# PCB-ETHMG-BOS.net
KiCad netlist of a schematic drawn in EAGLE
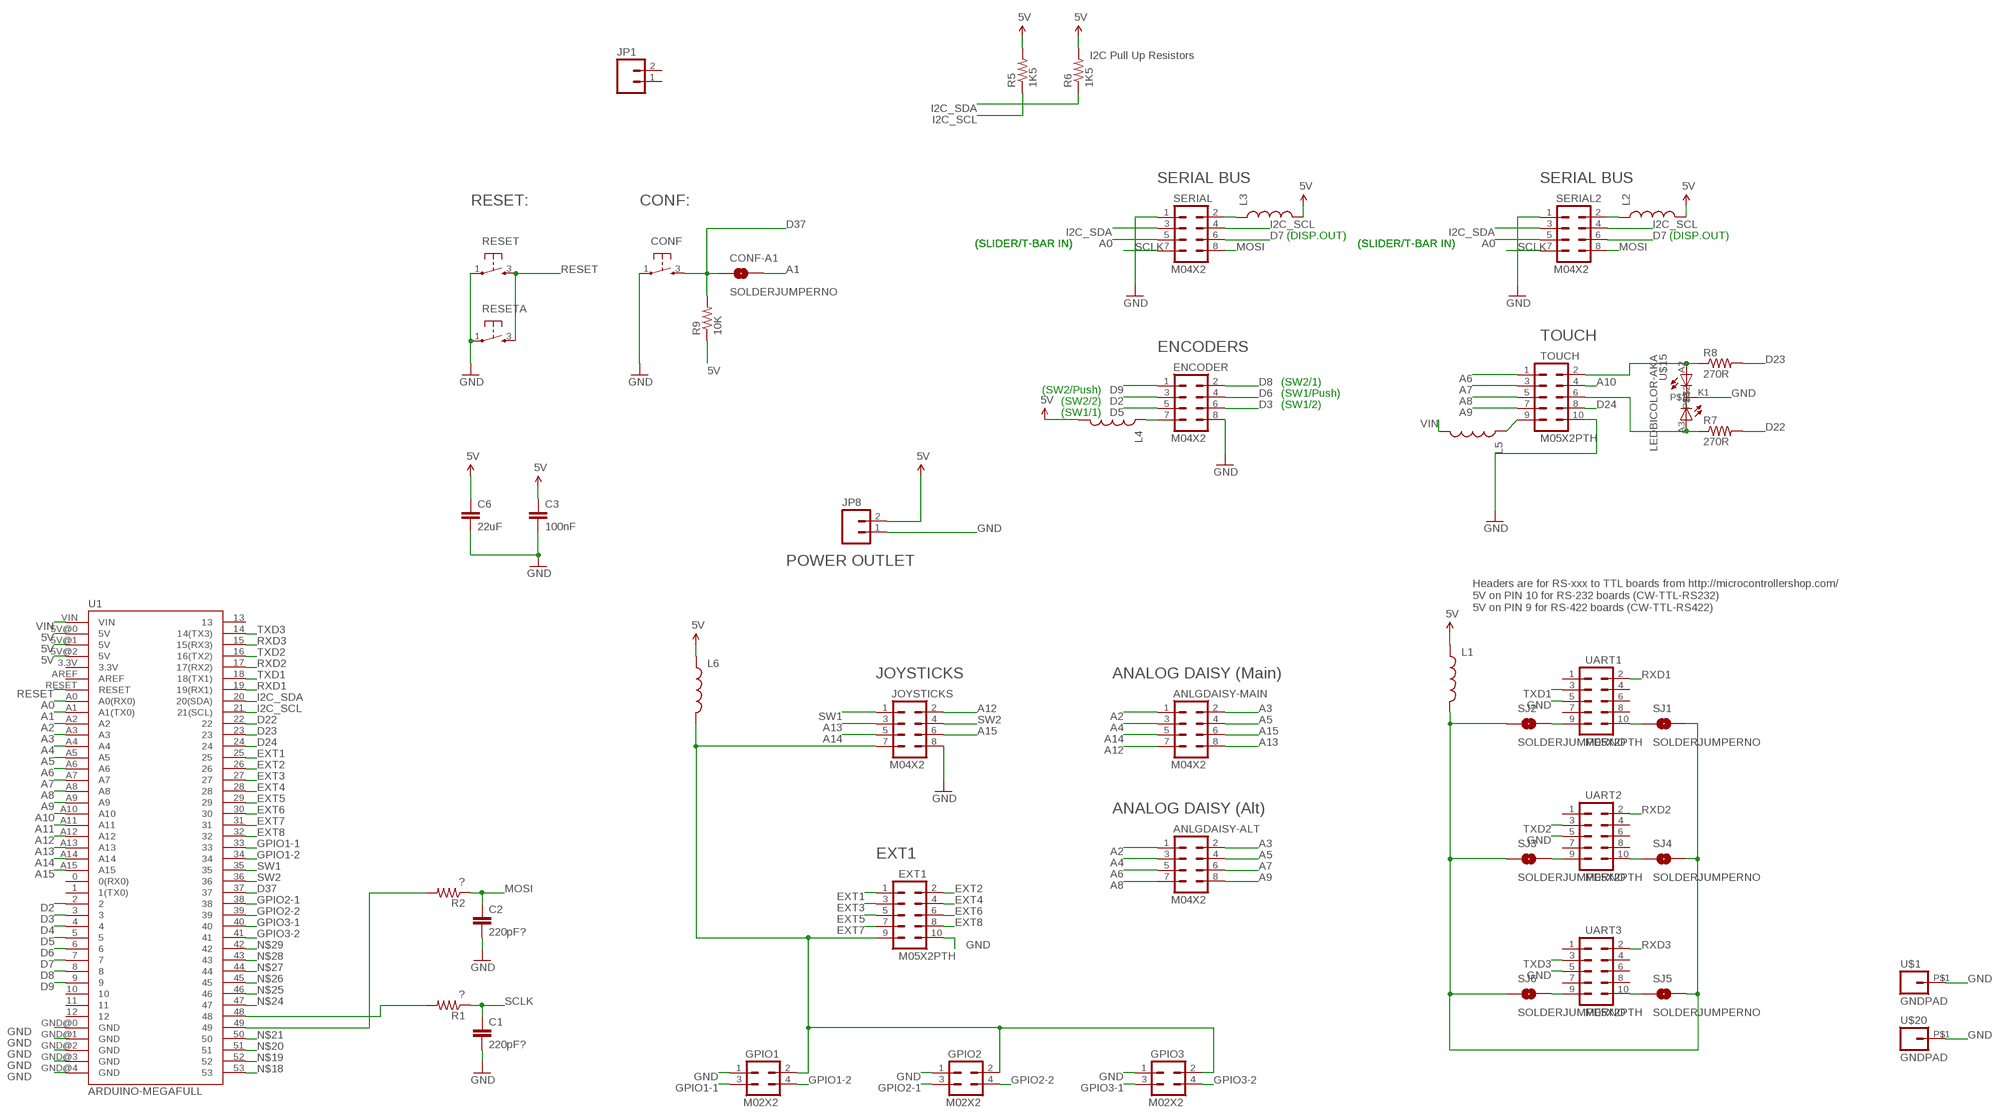
[diagram p0: schematic, sheet 1]

(export (version "E")
  (design (tool "Eeschema 10.0.6"))
  (components
    (comp (ref "ANLGDAISY-ALT")
      (value "M04X2")
      (footprint "eagle-import:2X4")
      (libsource (lib "eagle-import") (part "M04X2"))
    )
    (comp (ref "ANLGDAISY-MAIN")
      (value "M04X2")
      (footprint "eagle-import:2X4")
      (libsource (lib "eagle-import") (part "M04X2"))
    )
    (comp (ref "C1")
      (value "220pF?")
      (footprint "eagle-import:0603-CAP")
      (libsource (lib "eagle-import") (part "CAP0603-CAP"))
    )
    (comp (ref "C2")
      (value "220pF?")
      (footprint "eagle-import:0603-CAP")
      (libsource (lib "eagle-import") (part "CAP0603-CAP"))
    )
    (comp (ref "C3")
      (value "100nF")
      (footprint "eagle-import:0603-CAP")
      (libsource (lib "eagle-import") (part "CAP0603-CAP"))
    )
    (comp (ref "C6")
      (value "22uF")
      (footprint "eagle-import:0805")
      (libsource (lib "eagle-import") (part "CAP0805"))
    )
    (comp (ref "CONF")
      (value "TAC_SWITCH")
      (footprint "eagle-import:PUSHBUTTON")
      (libsource (lib "eagle-import") (part "TAC_SWITCH"))
    )
    (comp (ref "CONF-A1")
      (value "SOLDERJUMPERNO")
      (footprint "eagle-import:SJ_2S-NO")
      (libsource (lib "eagle-import") (part "SOLDERJUMPERNO"))
    )
    (comp (ref "ENCODER")
      (value "M04X2")
      (footprint "eagle-import:2X4")
      (libsource (lib "eagle-import") (part "M04X2"))
    )
    (comp (ref "EXT1")
      (value "M05X2PTH")
      (footprint "eagle-import:AVR_ICSP")
      (libsource (lib "eagle-import") (part "M05X2PTH"))
    )
    (comp (ref "GPIO1")
      (value "M02X2")
      (footprint "eagle-import:2X2")
      (libsource (lib "eagle-import") (part "M02X2"))
    )
    (comp (ref "GPIO2")
      (value "M02X2")
      (footprint "eagle-import:2X2")
      (libsource (lib "eagle-import") (part "M02X2"))
    )
    (comp (ref "GPIO3")
      (value "M02X2")
      (footprint "eagle-import:2X2")
      (libsource (lib "eagle-import") (part "M02X2"))
    )
    (comp (ref "JOYSTICKS")
      (value "M04X2")
      (footprint "eagle-import:2X4")
      (libsource (lib "eagle-import") (part "M04X2"))
    )
    (comp (ref "JP1")
      (value "M02PTH")
      (footprint "eagle-import:1X02")
      (libsource (lib "eagle-import") (part "M02PTH"))
    )
    (comp (ref "JP8")
      (value "M02PTH4")
      (footprint "eagle-import:1X02_XTRA_BIG")
      (libsource (lib "eagle-import") (part "M02PTH4"))
    )
    (comp (ref "L1")
      (value "INDUCTOR0805")
      (footprint "eagle-import:0805")
      (libsource (lib "eagle-import") (part "INDUCTOR0805"))
    )
    (comp (ref "L2")
      (value "INDUCTOR0805")
      (footprint "eagle-import:0805")
      (libsource (lib "eagle-import") (part "INDUCTOR0805"))
    )
    (comp (ref "L3")
      (value "INDUCTOR0805")
      (footprint "eagle-import:0805")
      (libsource (lib "eagle-import") (part "INDUCTOR0805"))
    )
    (comp (ref "L4")
      (value "INDUCTOR0805")
      (footprint "eagle-import:0805")
      (libsource (lib "eagle-import") (part "INDUCTOR0805"))
    )
    (comp (ref "L5")
      (value "INDUCTOR0805")
      (footprint "eagle-import:0805")
      (libsource (lib "eagle-import") (part "INDUCTOR0805"))
    )
    (comp (ref "L6")
      (value "INDUCTOR0805")
      (footprint "eagle-import:0805")
      (libsource (lib "eagle-import") (part "INDUCTOR0805"))
    )
    (comp (ref "R1")
      (value "?")
      (footprint "eagle-import:0603-RES")
      (libsource (lib "eagle-import") (part "RESISTOR0603-RES"))
    )
    (comp (ref "R2")
      (value "?")
      (footprint "eagle-import:0603-RES")
      (libsource (lib "eagle-import") (part "RESISTOR0603-RES"))
    )
    (comp (ref "R5")
      (value "1K5")
      (footprint "eagle-import:0603-RES")
      (libsource (lib "eagle-import") (part "RESISTOR0603-RES"))
    )
    (comp (ref "R6")
      (value "1K5")
      (footprint "eagle-import:0603-RES")
      (libsource (lib "eagle-import") (part "RESISTOR0603-RES"))
    )
    (comp (ref "R7")
      (value "270R")
      (footprint "eagle-import:0603-RES")
      (libsource (lib "eagle-import") (part "RESISTOR0603-RES"))
    )
    (comp (ref "R8")
      (value "270R")
      (footprint "eagle-import:0603-RES")
      (libsource (lib "eagle-import") (part "RESISTOR0603-RES"))
    )
    (comp (ref "R9")
      (value "10K")
      (footprint "eagle-import:0603-RES")
      (libsource (lib "eagle-import") (part "RESISTOR0603-RES"))
    )
    (comp (ref "RESET")
      (value "TAC_SWITCH")
      (footprint "eagle-import:PUSHBUTTON")
      (libsource (lib "eagle-import") (part "TAC_SWITCH"))
    )
    (comp (ref "RESETA")
      (value "TAC_SWITCH")
      (footprint "eagle-import:PUSHBUTTON")
      (libsource (lib "eagle-import") (part "TAC_SWITCH"))
    )
    (comp (ref "SERIAL")
      (value "M04X2")
      (footprint "eagle-import:2X4")
      (libsource (lib "eagle-import") (part "M04X2"))
    )
    (comp (ref "SERIAL2")
      (value "M04X2")
      (footprint "eagle-import:2X4")
      (libsource (lib "eagle-import") (part "M04X2"))
    )
    (comp (ref "SJ1")
      (value "SOLDERJUMPERNO")
      (footprint "eagle-import:SJ_2S-NO")
      (libsource (lib "eagle-import") (part "SOLDERJUMPERNO"))
    )
    (comp (ref "SJ2")
      (value "SOLDERJUMPERNO")
      (footprint "eagle-import:SJ_2S-NO")
      (libsource (lib "eagle-import") (part "SOLDERJUMPERNO"))
    )
    (comp (ref "SJ3")
      (value "SOLDERJUMPERNO")
      (footprint "eagle-import:SJ_2S-NO")
      (libsource (lib "eagle-import") (part "SOLDERJUMPERNO"))
    )
    (comp (ref "SJ4")
      (value "SOLDERJUMPERNO")
      (footprint "eagle-import:SJ_2S-NO")
      (libsource (lib "eagle-import") (part "SOLDERJUMPERNO"))
    )
    (comp (ref "SJ5")
      (value "SOLDERJUMPERNO")
      (footprint "eagle-import:SJ_2S-NO")
      (libsource (lib "eagle-import") (part "SOLDERJUMPERNO"))
    )
    (comp (ref "SJ6")
      (value "SOLDERJUMPERNO")
      (footprint "eagle-import:SJ_2S-NO")
      (libsource (lib "eagle-import") (part "SOLDERJUMPERNO"))
    )
    (comp (ref "TOUCH")
      (value "M05X2PTH")
      (footprint "eagle-import:AVR_ICSP")
      (libsource (lib "eagle-import") (part "M05X2PTH"))
    )
    (comp (ref "U$1")
      (value "GNDPAD")
      (footprint "eagle-import:3.2MMPAD")
      (libsource (lib "eagle-import") (part "GNDPAD"))
    )
    (comp (ref "U$15")
      (value "LEDBICOLOR-AKA")
      (footprint "eagle-import:LED5MM-BICOLOR")
      (libsource (lib "eagle-import") (part "LEDBICOLOR-AKA"))
    )
    (comp (ref "U$20")
      (value "GNDPAD")
      (footprint "eagle-import:3.2MMPAD")
      (libsource (lib "eagle-import") (part "GNDPAD"))
    )
    (comp (ref "U1")
      (value "ARDUINO-MEGAFULL")
      (footprint "eagle-import:ARDUINO_MEGA")
      (libsource (lib "eagle-import") (part "ARDUINO-MEGAFULL"))
    )
    (comp (ref "UART1")
      (value "M05X2PTH")
      (footprint "eagle-import:AVR_ICSP")
      (libsource (lib "eagle-import") (part "M05X2PTH"))
    )
    (comp (ref "UART2")
      (value "M05X2PTH")
      (footprint "eagle-import:AVR_ICSP")
      (libsource (lib "eagle-import") (part "M05X2PTH"))
    )
    (comp (ref "UART3")
      (value "M05X2PTH")
      (footprint "eagle-import:AVR_ICSP")
      (libsource (lib "eagle-import") (part "M05X2PTH"))
    )
  )
  (nets
    (net (code "1") (name "/A0") (class "Default")
      (node (ref "SERIAL") (pin "5") (pinfunction "5_5") (pintype "passive"))
      (node (ref "SERIAL2") (pin "5") (pinfunction "5_5") (pintype "passive"))
      (node (ref "U1") (pin "A0") (pinfunction "A0(RX0)_A0") (pintype "bidirectional"))
    )
    (net (code "2") (name "/A1") (class "Default")
      (node (ref "CONF-A1") (pin "2") (pinfunction "2_2") (pintype "passive"))
      (node (ref "U1") (pin "A1") (pinfunction "A1(TX0)_A1") (pintype "bidirectional"))
    )
    (net (code "3") (name "/A2") (class "Default")
      (node (ref "ANLGDAISY-ALT") (pin "1") (pinfunction "1_1") (pintype "passive"))
      (node (ref "ANLGDAISY-MAIN") (pin "1") (pinfunction "1_1") (pintype "passive"))
      (node (ref "U1") (pin "A2") (pinfunction "A2_A2") (pintype "bidirectional"))
    )
    (net (code "4") (name "/A3") (class "Default")
      (node (ref "ANLGDAISY-ALT") (pin "2") (pinfunction "2_2") (pintype "passive"))
      (node (ref "ANLGDAISY-MAIN") (pin "2") (pinfunction "2_2") (pintype "passive"))
      (node (ref "U1") (pin "A3") (pinfunction "A3_A3") (pintype "bidirectional"))
    )
    (net (code "5") (name "/A4") (class "Default")
      (node (ref "ANLGDAISY-ALT") (pin "3") (pinfunction "3_3") (pintype "passive"))
      (node (ref "ANLGDAISY-MAIN") (pin "3") (pinfunction "3_3") (pintype "passive"))
      (node (ref "U1") (pin "A4") (pinfunction "A4_A4") (pintype "bidirectional"))
    )
    (net (code "6") (name "/A5") (class "Default")
      (node (ref "ANLGDAISY-ALT") (pin "4") (pinfunction "4_4") (pintype "passive"))
      (node (ref "ANLGDAISY-MAIN") (pin "4") (pinfunction "4_4") (pintype "passive"))
      (node (ref "U1") (pin "A5") (pinfunction "A5_A5") (pintype "bidirectional"))
    )
    (net (code "7") (name "/A6") (class "Default")
      (node (ref "ANLGDAISY-ALT") (pin "5") (pinfunction "5_5") (pintype "passive"))
      (node (ref "TOUCH") (pin "1") (pinfunction "1_1") (pintype "passive"))
      (node (ref "U1") (pin "A6") (pinfunction "A6_A6") (pintype "bidirectional"))
    )
    (net (code "8") (name "/A7") (class "Default")
      (node (ref "ANLGDAISY-ALT") (pin "6") (pinfunction "6_6") (pintype "passive"))
      (node (ref "TOUCH") (pin "3") (pinfunction "3_3") (pintype "passive"))
      (node (ref "U1") (pin "A7") (pinfunction "A7_A7") (pintype "bidirectional"))
    )
    (net (code "9") (name "/A8") (class "Default")
      (node (ref "ANLGDAISY-ALT") (pin "7") (pinfunction "7_7") (pintype "passive"))
      (node (ref "TOUCH") (pin "5") (pinfunction "5_5") (pintype "passive"))
      (node (ref "U1") (pin "A8") (pinfunction "A8_A8") (pintype "bidirectional"))
    )
    (net (code "10") (name "/A9") (class "Default")
      (node (ref "ANLGDAISY-ALT") (pin "8") (pinfunction "8_8") (pintype "passive"))
      (node (ref "TOUCH") (pin "7") (pinfunction "7_7") (pintype "passive"))
      (node (ref "U1") (pin "A9") (pinfunction "A9_A9") (pintype "bidirectional"))
    )
    (net (code "11") (name "/A10") (class "Default")
      (node (ref "TOUCH") (pin "4") (pinfunction "4_4") (pintype "passive"))
      (node (ref "U1") (pin "A10") (pinfunction "A10_A10") (pintype "bidirectional"))
    )
    (net (code "12") (name "/A11") (class "Default")
      (node (ref "U1") (pin "A11") (pinfunction "A11_A11") (pintype "bidirectional"))
    )
    (net (code "13") (name "/A12") (class "Default")
      (node (ref "ANLGDAISY-MAIN") (pin "7") (pinfunction "7_7") (pintype "passive"))
      (node (ref "JOYSTICKS") (pin "2") (pinfunction "2_2") (pintype "passive"))
      (node (ref "U1") (pin "A12") (pinfunction "A12_A12") (pintype "bidirectional"))
    )
    (net (code "14") (name "/A13") (class "Default")
      (node (ref "ANLGDAISY-MAIN") (pin "8") (pinfunction "8_8") (pintype "passive"))
      (node (ref "JOYSTICKS") (pin "3") (pinfunction "3_3") (pintype "passive"))
      (node (ref "U1") (pin "A13") (pinfunction "A13_A13") (pintype "bidirectional"))
    )
    (net (code "15") (name "/A14") (class "Default")
      (node (ref "ANLGDAISY-MAIN") (pin "5") (pinfunction "5_5") (pintype "passive"))
      (node (ref "JOYSTICKS") (pin "5") (pinfunction "5_5") (pintype "passive"))
      (node (ref "U1") (pin "A14") (pinfunction "A14_A14") (pintype "bidirectional"))
    )
    (net (code "16") (name "/A15") (class "Default")
      (node (ref "ANLGDAISY-MAIN") (pin "6") (pinfunction "6_6") (pintype "passive"))
      (node (ref "JOYSTICKS") (pin "6") (pinfunction "6_6") (pintype "passive"))
      (node (ref "U1") (pin "A15") (pinfunction "A15_A15") (pintype "bidirectional"))
    )
    (net (code "17") (name "/D2") (class "Default")
      (node (ref "ENCODER") (pin "3") (pinfunction "3_3") (pintype "passive"))
      (node (ref "U1") (pin "2") (pinfunction "2_2") (pintype "bidirectional"))
    )
    (net (code "18") (name "/D3") (class "Default")
      (node (ref "ENCODER") (pin "6") (pinfunction "6_6") (pintype "passive"))
      (node (ref "U1") (pin "3") (pinfunction "3_3") (pintype "bidirectional"))
    )
    (net (code "19") (name "/D4") (class "Default")
      (node (ref "U1") (pin "4") (pinfunction "4_4") (pintype "bidirectional"))
    )
    (net (code "20") (name "/D5") (class "Default")
      (node (ref "ENCODER") (pin "5") (pinfunction "5_5") (pintype "passive"))
      (node (ref "U1") (pin "5") (pinfunction "5_5") (pintype "bidirectional"))
    )
    (net (code "21") (name "/D6") (class "Default")
      (node (ref "ENCODER") (pin "4") (pinfunction "4_4") (pintype "passive"))
      (node (ref "U1") (pin "6") (pinfunction "6_6") (pintype "bidirectional"))
    )
    (net (code "22") (name "/D7") (class "Default")
      (node (ref "SERIAL") (pin "6") (pinfunction "6_6") (pintype "passive"))
      (node (ref "SERIAL2") (pin "6") (pinfunction "6_6") (pintype "passive"))
      (node (ref "U1") (pin "7") (pinfunction "7_7") (pintype "bidirectional"))
    )
    (net (code "23") (name "/D8") (class "Default")
      (node (ref "ENCODER") (pin "2") (pinfunction "2_2") (pintype "passive"))
      (node (ref "U1") (pin "8") (pinfunction "8_8") (pintype "bidirectional"))
    )
    (net (code "24") (name "/D9") (class "Default")
      (node (ref "ENCODER") (pin "1") (pinfunction "1_1") (pintype "passive"))
      (node (ref "U1") (pin "9") (pinfunction "9_9") (pintype "bidirectional"))
    )
    (net (code "25") (name "/D22") (class "Default")
      (node (ref "R7") (pin "2") (pinfunction "2_2") (pintype "passive"))
      (node (ref "U1") (pin "22") (pinfunction "22_22") (pintype "bidirectional"))
    )
    (net (code "26") (name "/D23") (class "Default")
      (node (ref "R8") (pin "2") (pinfunction "2_2") (pintype "passive"))
      (node (ref "U1") (pin "23") (pinfunction "23_23") (pintype "bidirectional"))
    )
    (net (code "27") (name "/D24") (class "Default")
      (node (ref "TOUCH") (pin "8") (pinfunction "8_8") (pintype "passive"))
      (node (ref "U1") (pin "24") (pinfunction "24_24") (pintype "bidirectional"))
    )
    (net (code "28") (name "/D37") (class "Default")
      (node (ref "CONF") (pin "3") (pinfunction "3_3") (pintype "passive"))
      (node (ref "CONF-A1") (pin "1") (pinfunction "1_1") (pintype "passive"))
      (node (ref "R9") (pin "2") (pinfunction "2_2") (pintype "passive"))
      (node (ref "U1") (pin "37") (pinfunction "37_37") (pintype "bidirectional"))
    )
    (net (code "29") (name "/EXT1") (class "Default")
      (node (ref "EXT1") (pin "1") (pinfunction "1_1") (pintype "passive"))
      (node (ref "U1") (pin "25") (pinfunction "25_25") (pintype "bidirectional"))
    )
    (net (code "30") (name "/EXT2") (class "Default")
      (node (ref "EXT1") (pin "2") (pinfunction "2_2") (pintype "passive"))
      (node (ref "U1") (pin "26") (pinfunction "26_26") (pintype "bidirectional"))
    )
    (net (code "31") (name "/EXT3") (class "Default")
      (node (ref "EXT1") (pin "3") (pinfunction "3_3") (pintype "passive"))
      (node (ref "U1") (pin "27") (pinfunction "27_27") (pintype "bidirectional"))
    )
    (net (code "32") (name "/EXT4") (class "Default")
      (node (ref "EXT1") (pin "4") (pinfunction "4_4") (pintype "passive"))
      (node (ref "U1") (pin "28") (pinfunction "28_28") (pintype "bidirectional"))
    )
    (net (code "33") (name "/EXT5") (class "Default")
      (node (ref "EXT1") (pin "5") (pinfunction "5_5") (pintype "passive"))
      (node (ref "U1") (pin "29") (pinfunction "29_29") (pintype "bidirectional"))
    )
    (net (code "34") (name "/EXT6") (class "Default")
      (node (ref "EXT1") (pin "6") (pinfunction "6_6") (pintype "passive"))
      (node (ref "U1") (pin "30") (pinfunction "30_30") (pintype "bidirectional"))
    )
    (net (code "35") (name "/EXT7") (class "Default")
      (node (ref "EXT1") (pin "7") (pinfunction "7_7") (pintype "passive"))
      (node (ref "U1") (pin "31") (pinfunction "31_31") (pintype "bidirectional"))
    )
    (net (code "36") (name "/EXT8") (class "Default")
      (node (ref "EXT1") (pin "8") (pinfunction "8_8") (pintype "passive"))
      (node (ref "U1") (pin "32") (pinfunction "32_32") (pintype "bidirectional"))
    )
    (net (code "37") (name "/GPIO1-1") (class "Default")
      (node (ref "GPIO1") (pin "3") (pinfunction "3_3") (pintype "passive"))
      (node (ref "U1") (pin "33") (pinfunction "33_33") (pintype "bidirectional"))
    )
    (net (code "38") (name "/GPIO1-2") (class "Default")
      (node (ref "GPIO1") (pin "4") (pinfunction "4_4") (pintype "passive"))
      (node (ref "U1") (pin "34") (pinfunction "34_34") (pintype "bidirectional"))
    )
    (net (code "39") (name "/GPIO2-1") (class "Default")
      (node (ref "GPIO2") (pin "3") (pinfunction "3_3") (pintype "passive"))
      (node (ref "U1") (pin "38") (pinfunction "38_38") (pintype "bidirectional"))
    )
    (net (code "40") (name "/GPIO2-2") (class "Default")
      (node (ref "GPIO2") (pin "4") (pinfunction "4_4") (pintype "passive"))
      (node (ref "U1") (pin "39") (pinfunction "39_39") (pintype "bidirectional"))
    )
    (net (code "41") (name "/GPIO3-1") (class "Default")
      (node (ref "GPIO3") (pin "3") (pinfunction "3_3") (pintype "passive"))
      (node (ref "U1") (pin "40") (pinfunction "40_40") (pintype "bidirectional"))
    )
    (net (code "42") (name "/GPIO3-2") (class "Default")
      (node (ref "GPIO3") (pin "4") (pinfunction "4_4") (pintype "passive"))
      (node (ref "U1") (pin "41") (pinfunction "41_41") (pintype "bidirectional"))
    )
    (net (code "43") (name "/I2C_SCL") (class "Default")
      (node (ref "R5") (pin "1") (pinfunction "1_1") (pintype "passive"))
      (node (ref "SERIAL") (pin "4") (pinfunction "4_4") (pintype "passive"))
      (node (ref "SERIAL2") (pin "4") (pinfunction "4_4") (pintype "passive"))
      (node (ref "U1") (pin "21") (pinfunction "21(SCL)_21") (pintype "bidirectional"))
    )
    (net (code "44") (name "/I2C_SDA") (class "Default")
      (node (ref "R6") (pin "1") (pinfunction "1_1") (pintype "passive"))
      (node (ref "SERIAL") (pin "3") (pinfunction "3_3") (pintype "passive"))
      (node (ref "SERIAL2") (pin "3") (pinfunction "3_3") (pintype "passive"))
      (node (ref "U1") (pin "20") (pinfunction "20(SDA)_20") (pintype "bidirectional"))
    )
    (net (code "45") (name "/MOSI") (class "Default")
      (node (ref "C2") (pin "1") (pinfunction "1_1") (pintype "passive"))
      (node (ref "R2") (pin "1") (pinfunction "1_1") (pintype "passive"))
      (node (ref "SERIAL") (pin "8") (pinfunction "8_8") (pintype "passive"))
      (node (ref "SERIAL2") (pin "8") (pinfunction "8_8") (pintype "passive"))
    )
    (net (code "46") (name "/N$18") (class "Default")
      (node (ref "U1") (pin "53") (pinfunction "53_53") (pintype "bidirectional"))
    )
    (net (code "47") (name "/N$19") (class "Default")
      (node (ref "U1") (pin "52") (pinfunction "52_52") (pintype "bidirectional"))
    )
    (net (code "48") (name "/N$20") (class "Default")
      (node (ref "U1") (pin "51") (pinfunction "51_51") (pintype "bidirectional"))
    )
    (net (code "49") (name "/N$21") (class "Default")
      (node (ref "U1") (pin "50") (pinfunction "50_50") (pintype "bidirectional"))
    )
    (net (code "50") (name "/N$24") (class "Default")
      (node (ref "U1") (pin "47") (pinfunction "47_47") (pintype "bidirectional"))
    )
    (net (code "51") (name "/N$25") (class "Default")
      (node (ref "U1") (pin "46") (pinfunction "46_46") (pintype "bidirectional"))
    )
    (net (code "52") (name "/N$26") (class "Default")
      (node (ref "U1") (pin "45") (pinfunction "45_45") (pintype "bidirectional"))
    )
    (net (code "53") (name "/N$27") (class "Default")
      (node (ref "U1") (pin "44") (pinfunction "44_44") (pintype "bidirectional"))
    )
    (net (code "54") (name "/N$28") (class "Default")
      (node (ref "U1") (pin "43") (pinfunction "43_43") (pintype "bidirectional"))
    )
    (net (code "55") (name "/N$29") (class "Default")
      (node (ref "U1") (pin "42") (pinfunction "42_42") (pintype "bidirectional"))
    )
    (net (code "56") (name "/RESET") (class "Default")
      (node (ref "RESET") (pin "3") (pinfunction "3_3") (pintype "passive"))
      (node (ref "RESETA") (pin "3") (pinfunction "3_3") (pintype "passive"))
      (node (ref "U1") (pin "RESET") (pinfunction "RESET_RESET") (pintype "bidirectional"))
    )
    (net (code "57") (name "/RXD1") (class "Default")
      (node (ref "U1") (pin "19") (pinfunction "19(RX1)_19") (pintype "bidirectional"))
      (node (ref "UART1") (pin "2") (pinfunction "2_2") (pintype "passive"))
    )
    (net (code "58") (name "/RXD2") (class "Default")
      (node (ref "U1") (pin "17") (pinfunction "17(RX2)_17") (pintype "bidirectional"))
      (node (ref "UART2") (pin "2") (pinfunction "2_2") (pintype "passive"))
    )
    (net (code "59") (name "/RXD3") (class "Default")
      (node (ref "U1") (pin "15") (pinfunction "15(RX3)_15") (pintype "bidirectional"))
      (node (ref "UART3") (pin "2") (pinfunction "2_2") (pintype "passive"))
    )
    (net (code "60") (name "/SCLK") (class "Default")
      (node (ref "C1") (pin "1") (pinfunction "1_1") (pintype "passive"))
      (node (ref "R1") (pin "1") (pinfunction "1_1") (pintype "passive"))
      (node (ref "SERIAL") (pin "7") (pinfunction "7_7") (pintype "passive"))
      (node (ref "SERIAL2") (pin "7") (pinfunction "7_7") (pintype "passive"))
    )
    (net (code "61") (name "/SW1") (class "Default")
      (node (ref "JOYSTICKS") (pin "1") (pinfunction "1_1") (pintype "passive"))
      (node (ref "U1") (pin "35") (pinfunction "35_35") (pintype "bidirectional"))
    )
    (net (code "62") (name "/SW2") (class "Default")
      (node (ref "JOYSTICKS") (pin "4") (pinfunction "4_4") (pintype "passive"))
      (node (ref "U1") (pin "36") (pinfunction "36_36") (pintype "bidirectional"))
    )
    (net (code "63") (name "/TXD1") (class "Default")
      (node (ref "U1") (pin "18") (pinfunction "18(TX1)_18") (pintype "bidirectional"))
      (node (ref "UART1") (pin "3") (pinfunction "3_3") (pintype "passive"))
    )
    (net (code "64") (name "/TXD2") (class "Default")
      (node (ref "U1") (pin "16") (pinfunction "16(TX2)_16") (pintype "bidirectional"))
      (node (ref "UART2") (pin "3") (pinfunction "3_3") (pintype "passive"))
    )
    (net (code "65") (name "/TXD3") (class "Default")
      (node (ref "U1") (pin "14") (pinfunction "14(TX3)_14") (pintype "bidirectional"))
      (node (ref "UART3") (pin "3") (pinfunction "3_3") (pintype "passive"))
    )
    (net (code "66") (name "/VIN") (class "Default")
      (node (ref "L5") (pin "2") (pinfunction "2_2") (pintype "passive"))
      (node (ref "U1") (pin "VIN") (pinfunction "VIN_VIN") (pintype "bidirectional"))
    )
    (net (code "67") (name "5V") (class "Default")
      (node (ref "C3") (pin "1") (pinfunction "1_1") (pintype "passive"))
      (node (ref "C6") (pin "1") (pinfunction "1_1") (pintype "passive"))
      (node (ref "JP8") (pin "2") (pinfunction "2_2") (pintype "passive"))
      (node (ref "L1") (pin "1") (pinfunction "1_1") (pintype "passive"))
      (node (ref "L2") (pin "2") (pinfunction "2_2") (pintype "passive"))
      (node (ref "L3") (pin "2") (pinfunction "2_2") (pintype "passive"))
      (node (ref "L4") (pin "2") (pinfunction "2_2") (pintype "passive"))
      (node (ref "L6") (pin "1") (pinfunction "1_1") (pintype "passive"))
      (node (ref "R5") (pin "2") (pinfunction "2_2") (pintype "passive"))
      (node (ref "R6") (pin "2") (pinfunction "2_2") (pintype "passive"))
      (node (ref "R9") (pin "1") (pinfunction "1_1") (pintype "passive"))
      (node (ref "U1") (pin "5V@0") (pinfunction "5V_5V@0") (pintype "bidirectional"))
      (node (ref "U1") (pin "5V@1") (pinfunction "5V_5V@1") (pintype "bidirectional"))
      (node (ref "U1") (pin "5V@2") (pinfunction "5V_5V@2") (pintype "bidirectional"))
    )
    (net (code "68") (name "GND") (class "Default")
      (node (ref "C1") (pin "2") (pinfunction "2_2") (pintype "passive"))
      (node (ref "C2") (pin "2") (pinfunction "2_2") (pintype "passive"))
      (node (ref "C3") (pin "2") (pinfunction "2_2") (pintype "passive"))
      (node (ref "C6") (pin "2") (pinfunction "2_2") (pintype "passive"))
      (node (ref "CONF") (pin "1") (pinfunction "1_1") (pintype "passive"))
      (node (ref "ENCODER") (pin "8") (pinfunction "8_8") (pintype "passive"))
      (node (ref "EXT1") (pin "10") (pinfunction "10_10") (pintype "passive"))
      (node (ref "GPIO1") (pin "1") (pinfunction "1_1") (pintype "passive"))
      (node (ref "GPIO2") (pin "1") (pinfunction "1_1") (pintype "passive"))
      (node (ref "GPIO3") (pin "1") (pinfunction "1_1") (pintype "passive"))
      (node (ref "JOYSTICKS") (pin "8") (pinfunction "8_8") (pintype "passive"))
      (node (ref "JP8") (pin "1") (pinfunction "1_1") (pintype "passive"))
      (node (ref "RESET") (pin "1") (pinfunction "1_1") (pintype "passive"))
      (node (ref "RESETA") (pin "1") (pinfunction "1_1") (pintype "passive"))
      (node (ref "SERIAL") (pin "1") (pinfunction "1_1") (pintype "passive"))
      (node (ref "SERIAL2") (pin "1") (pinfunction "1_1") (pintype "passive"))
      (node (ref "TOUCH") (pin "10") (pinfunction "10_10") (pintype "passive"))
      (node (ref "U$1") (pin "P$1") (pinfunction "1_P$1") (pintype "passive"))
      (node (ref "U$15") (pin "K1") (pinfunction "P$1_K1") (pintype "bidirectional"))
      (node (ref "U$20") (pin "P$1") (pinfunction "1_P$1") (pintype "passive"))
      (node (ref "U1") (pin "GND@0") (pinfunction "GND_GND@0") (pintype "bidirectional"))
      (node (ref "U1") (pin "GND@1") (pinfunction "GND_GND@1") (pintype "bidirectional"))
      (node (ref "U1") (pin "GND@2") (pinfunction "GND_GND@2") (pintype "bidirectional"))
      (node (ref "U1") (pin "GND@3") (pinfunction "GND_GND@3") (pintype "bidirectional"))
      (node (ref "U1") (pin "GND@4") (pinfunction "GND_GND@4") (pintype "bidirectional"))
      (node (ref "UART1") (pin "5") (pinfunction "5_5") (pintype "passive"))
      (node (ref "UART2") (pin "5") (pinfunction "5_5") (pintype "passive"))
      (node (ref "UART3") (pin "5") (pinfunction "5_5") (pintype "passive"))
    )
    (net (code "69") (name "Net-(ENCODER-Pad7)") (class "Default")
      (node (ref "ENCODER") (pin "7") (pinfunction "7_7") (pintype "passive"))
      (node (ref "L4") (pin "1") (pinfunction "1_1") (pintype "passive"))
    )
    (net (code "70") (name "Net-(EXT1-Pad9)") (class "Default")
      (node (ref "EXT1") (pin "9") (pinfunction "9_9") (pintype "passive"))
      (node (ref "GPIO1") (pin "2") (pinfunction "2_2") (pintype "passive"))
      (node (ref "GPIO2") (pin "2") (pinfunction "2_2") (pintype "passive"))
      (node (ref "GPIO3") (pin "2") (pinfunction "2_2") (pintype "passive"))
      (node (ref "JOYSTICKS") (pin "7") (pinfunction "7_7") (pintype "passive"))
      (node (ref "L6") (pin "2") (pinfunction "2_2") (pintype "passive"))
    )
    (net (code "71") (name "Net-(L1-Pad2)") (class "Default")
      (node (ref "L1") (pin "2") (pinfunction "2_2") (pintype "passive"))
      (node (ref "SJ1") (pin "2") (pinfunction "2_2") (pintype "passive"))
      (node (ref "SJ2") (pin "1") (pinfunction "1_1") (pintype "passive"))
      (node (ref "SJ3") (pin "1") (pinfunction "1_1") (pintype "passive"))
      (node (ref "SJ4") (pin "2") (pinfunction "2_2") (pintype "passive"))
      (node (ref "SJ5") (pin "2") (pinfunction "2_2") (pintype "passive"))
      (node (ref "SJ6") (pin "1") (pinfunction "1_1") (pintype "passive"))
    )
    (net (code "72") (name "Net-(L2-Pad1)") (class "Default")
      (node (ref "L2") (pin "1") (pinfunction "1_1") (pintype "passive"))
      (node (ref "SERIAL2") (pin "2") (pinfunction "2_2") (pintype "passive"))
    )
    (net (code "73") (name "Net-(L3-Pad1)") (class "Default")
      (node (ref "L3") (pin "1") (pinfunction "1_1") (pintype "passive"))
      (node (ref "SERIAL") (pin "2") (pinfunction "2_2") (pintype "passive"))
    )
    (net (code "74") (name "Net-(L5-Pad1)") (class "Default")
      (node (ref "L5") (pin "1") (pinfunction "1_1") (pintype "passive"))
      (node (ref "TOUCH") (pin "9") (pinfunction "9_9") (pintype "passive"))
    )
    (net (code "75") (name "Net-(R1-Pad2)") (class "Default")
      (node (ref "R1") (pin "2") (pinfunction "2_2") (pintype "passive"))
      (node (ref "U1") (pin "48") (pinfunction "48_48") (pintype "bidirectional"))
    )
    (net (code "76") (name "Net-(R2-Pad2)") (class "Default")
      (node (ref "R2") (pin "2") (pinfunction "2_2") (pintype "passive"))
      (node (ref "U1") (pin "49") (pinfunction "49_49") (pintype "bidirectional"))
    )
    (net (code "77") (name "Net-(SJ1-Pad1)") (class "Default")
      (node (ref "SJ1") (pin "1") (pinfunction "1_1") (pintype "passive"))
      (node (ref "UART1") (pin "10") (pinfunction "10_10") (pintype "passive"))
    )
    (net (code "78") (name "Net-(SJ2-Pad2)") (class "Default")
      (node (ref "SJ2") (pin "2") (pinfunction "2_2") (pintype "passive"))
      (node (ref "UART1") (pin "9") (pinfunction "9_9") (pintype "passive"))
    )
    (net (code "79") (name "Net-(SJ3-Pad2)") (class "Default")
      (node (ref "SJ3") (pin "2") (pinfunction "2_2") (pintype "passive"))
      (node (ref "UART2") (pin "9") (pinfunction "9_9") (pintype "passive"))
    )
    (net (code "80") (name "Net-(SJ4-Pad1)") (class "Default")
      (node (ref "SJ4") (pin "1") (pinfunction "1_1") (pintype "passive"))
      (node (ref "UART2") (pin "10") (pinfunction "10_10") (pintype "passive"))
    )
    (net (code "81") (name "Net-(SJ5-Pad1)") (class "Default")
      (node (ref "SJ5") (pin "1") (pinfunction "1_1") (pintype "passive"))
      (node (ref "UART3") (pin "10") (pinfunction "10_10") (pintype "passive"))
    )
    (net (code "82") (name "Net-(SJ6-Pad2)") (class "Default")
      (node (ref "SJ6") (pin "2") (pinfunction "2_2") (pintype "passive"))
      (node (ref "UART3") (pin "9") (pinfunction "9_9") (pintype "passive"))
    )
    (net (code "83") (name "Net-(U$15-P$2)") (class "Default")
      (node (ref "R8") (pin "1") (pinfunction "1_1") (pintype "passive"))
      (node (ref "TOUCH") (pin "2") (pinfunction "2_2") (pintype "passive"))
      (node (ref "U$15") (pin "A2") (pinfunction "P$2_A2") (pintype "bidirectional"))
    )
    (net (code "84") (name "Net-(U$15-P$3)") (class "Default")
      (node (ref "R7") (pin "1") (pinfunction "1_1") (pintype "passive"))
      (node (ref "TOUCH") (pin "6") (pinfunction "6_6") (pintype "passive"))
      (node (ref "U$15") (pin "A3") (pinfunction "P$3_A3") (pintype "bidirectional"))
    )
    (net (code "85") (name "unconnected-(JP1-Pad1)") (class "Default")
      (node (ref "JP1") (pin "1") (pinfunction "1_1") (pintype "passive"))
    )
    (net (code "86") (name "unconnected-(JP1-Pad2)") (class "Default")
      (node (ref "JP1") (pin "2") (pinfunction "2_2") (pintype "passive"))
    )
    (net (code "87") (name "unconnected-(U1-0(RX0)-Pad0)") (class "Default")
      (node (ref "U1") (pin "0") (pinfunction "0(RX0)_0") (pintype "bidirectional"))
    )
    (net (code "88") (name "unconnected-(U1-1(TX0)-Pad1)") (class "Default")
      (node (ref "U1") (pin "1") (pinfunction "1(TX0)_1") (pintype "bidirectional"))
    )
    (net (code "89") (name "unconnected-(U1-Pad3.3V)") (class "Default")
      (node (ref "U1") (pin "3.3V") (pinfunction "3.3V_3.3V") (pintype "bidirectional"))
    )
    (net (code "90") (name "unconnected-(U1-Pad10)") (class "Default")
      (node (ref "U1") (pin "10") (pinfunction "10_10") (pintype "bidirectional"))
    )
    (net (code "91") (name "unconnected-(U1-Pad11)") (class "Default")
      (node (ref "U1") (pin "11") (pinfunction "11_11") (pintype "bidirectional"))
    )
    (net (code "92") (name "unconnected-(U1-Pad12)") (class "Default")
      (node (ref "U1") (pin "12") (pinfunction "12_12") (pintype "bidirectional"))
    )
    (net (code "93") (name "unconnected-(U1-Pad13)") (class "Default")
      (node (ref "U1") (pin "13") (pinfunction "13_13") (pintype "bidirectional"))
    )
    (net (code "94") (name "unconnected-(U1-PadAREF)") (class "Default")
      (node (ref "U1") (pin "AREF") (pinfunction "AREF_AREF") (pintype "bidirectional"))
    )
    (net (code "95") (name "unconnected-(UART1-Pad1)") (class "Default")
      (node (ref "UART1") (pin "1") (pinfunction "1_1") (pintype "passive"))
    )
    (net (code "96") (name "unconnected-(UART1-Pad4)") (class "Default")
      (node (ref "UART1") (pin "4") (pinfunction "4_4") (pintype "passive"))
    )
    (net (code "97") (name "unconnected-(UART1-Pad6)") (class "Default")
      (node (ref "UART1") (pin "6") (pinfunction "6_6") (pintype "passive"))
    )
    (net (code "98") (name "unconnected-(UART1-Pad7)") (class "Default")
      (node (ref "UART1") (pin "7") (pinfunction "7_7") (pintype "passive"))
    )
    (net (code "99") (name "unconnected-(UART1-Pad8)") (class "Default")
      (node (ref "UART1") (pin "8") (pinfunction "8_8") (pintype "passive"))
    )
    (net (code "100") (name "unconnected-(UART2-Pad1)") (class "Default")
      (node (ref "UART2") (pin "1") (pinfunction "1_1") (pintype "passive"))
    )
    (net (code "101") (name "unconnected-(UART2-Pad4)") (class "Default")
      (node (ref "UART2") (pin "4") (pinfunction "4_4") (pintype "passive"))
    )
    (net (code "102") (name "unconnected-(UART2-Pad6)") (class "Default")
      (node (ref "UART2") (pin "6") (pinfunction "6_6") (pintype "passive"))
    )
    (net (code "103") (name "unconnected-(UART2-Pad7)") (class "Default")
      (node (ref "UART2") (pin "7") (pinfunction "7_7") (pintype "passive"))
    )
    (net (code "104") (name "unconnected-(UART2-Pad8)") (class "Default")
      (node (ref "UART2") (pin "8") (pinfunction "8_8") (pintype "passive"))
    )
    (net (code "105") (name "unconnected-(UART3-Pad1)") (class "Default")
      (node (ref "UART3") (pin "1") (pinfunction "1_1") (pintype "passive"))
    )
    (net (code "106") (name "unconnected-(UART3-Pad4)") (class "Default")
      (node (ref "UART3") (pin "4") (pinfunction "4_4") (pintype "passive"))
    )
    (net (code "107") (name "unconnected-(UART3-Pad6)") (class "Default")
      (node (ref "UART3") (pin "6") (pinfunction "6_6") (pintype "passive"))
    )
    (net (code "108") (name "unconnected-(UART3-Pad7)") (class "Default")
      (node (ref "UART3") (pin "7") (pinfunction "7_7") (pintype "passive"))
    )
    (net (code "109") (name "unconnected-(UART3-Pad8)") (class "Default")
      (node (ref "UART3") (pin "8") (pinfunction "8_8") (pintype "passive"))
    )
  )
)
